# CAN.net
KiCad netlist of a schematic drawn in Altium Designer
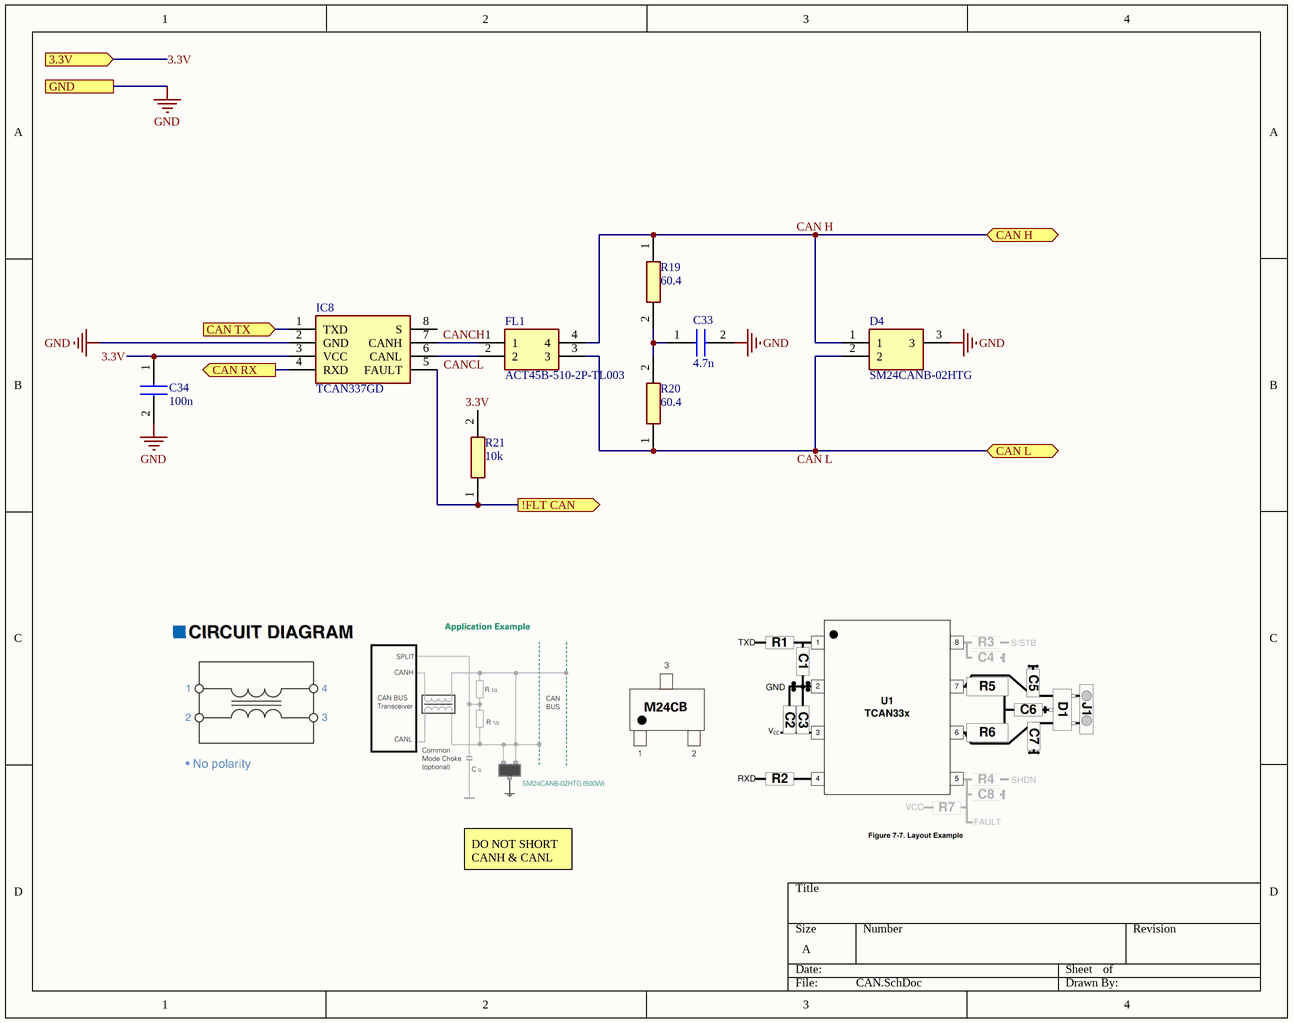
[diagram p0: CAN.SchDoc]

(export (version "E")
  (design (tool "Eeschema 10.0.6"))
  (components
    (comp (ref "C33")
      (value "4.7n")
      (footprint "SamacSys:CAPC3216X75N")
      (description "Capacitor")
      (fields
        (field (name "MANUFACTURER_PART_NUMBER") "KAM31GR71H475KL")
        (field (name "MOUSER PART NUMBER") "581-KAM31GR71H475KL")
      )
      (libsource (lib "*") (part "KAM31GR71H475KL"))
    )
    (comp (ref "C34")
      (value "100n")
      (footprint "SamacSys:CAPC3216X94N")
      (description "Capacitor")
      (fields
        (field (name "MANUFACTURER_PART_NUMBER") "12065C104J4Z2A")
        (field (name "MOUSER PART NUMBER") "581-12065C104J4Z2A")
      )
      (libsource (lib "SamacSys") (part "12065C104J4Z2A"))
    )
    (comp (ref "D4")
      (value "SM24CANB-02HTG")
      (footprint "SamacSys:SM24CANB02HTG")
      (description "TVS Diode (Bi-directional)")
      (fields (field (name "MOUSER PART NUMBER") "576-SM24CANB-02HTG"))
      (libsource (lib "*") (part "SM24CANB-02HTG"))
    )
    (comp (ref "FL1")
      (value "ACT45B-510-2P-TL003")
      (footprint "SamacSys:ACT45B1012PTL003")
      (description "Filter")
      (fields (field (name "MOUSER PART NUMBER") "810-ACT45B5102PTL003"))
      (libsource (lib "*") (part "ACT45B-510-2P-TL003"))
    )
    (comp (ref "IC8")
      (value "TCAN337GD")
      (footprint "SamacSys:SOIC127P600X175-8N")
      (description "Integrated Circuit")
      (fields (field (name "MOUSER PART NUMBER") "595-TCAN337GD"))
      (libsource (lib "*") (part "TCAN337GD"))
    )
    (comp (ref "R19")
      (value "60.4")
      (footprint "SamacSys:RESC3216X65N")
      (description "Resistor")
      (fields (field (name "MANUFACTURER_PART_NUMBER") "ESR18EZPF60R4"))
      (libsource (lib "*") (part "ESR18EZPF60R4"))
    )
    (comp (ref "R20")
      (value "60.4")
      (footprint "SamacSys:RESC3216X65N")
      (description "Resistor")
      (fields (field (name "MANUFACTURER_PART_NUMBER") "ESR18EZPF60R4"))
      (libsource (lib "") (part "ESR18EZPF60R4_1"))
    )
    (comp (ref "R21")
      (value "10k")
      (footprint "SamacSys:RESC3216X65N")
      (description "Resistor")
      (fields (field (name "MANUFACTURER_PART_NUMBER") "SFR18EZPJ103"))
      (libsource (lib "*") (part "SFR18EZPJ103"))
    )
  )
  (nets
    (net (code "1") (name "/!FLT CAN") (class "Default")
      (node (ref "IC8") (pin "5") (pinfunction "FAULT_5") (pintype "passive"))
      (node (ref "R21") (pin "1") (pinfunction "1_1") (pintype "passive"))
    )
    (net (code "2") (name "/3.3V") (class "Default")
      (node (ref "C34") (pin "1") (pinfunction "1_1") (pintype "passive"))
      (node (ref "IC8") (pin "3") (pinfunction "VCC_3") (pintype "passive"))
      (node (ref "R21") (pin "2") (pinfunction "2_2") (pintype "passive"))
    )
    (net (code "3") (name "/CAN H") (class "Default")
      (node (ref "D4") (pin "1") (pinfunction "1_1") (pintype "passive"))
      (node (ref "FL1") (pin "4") (pinfunction "4_4") (pintype "passive"))
      (node (ref "R19") (pin "1") (pinfunction "1_1") (pintype "passive"))
    )
    (net (code "4") (name "/CAN L") (class "Default")
      (node (ref "D4") (pin "2") (pinfunction "2_2") (pintype "passive"))
      (node (ref "FL1") (pin "3") (pinfunction "3_3") (pintype "passive"))
      (node (ref "R20") (pin "1") (pinfunction "1_1") (pintype "passive"))
    )
    (net (code "5") (name "/CAN RX") (class "Default")
      (node (ref "IC8") (pin "4") (pinfunction "RXD_4") (pintype "passive"))
    )
    (net (code "6") (name "/CAN TX") (class "Default")
      (node (ref "IC8") (pin "1") (pinfunction "TXD_1") (pintype "passive"))
    )
    (net (code "7") (name "/CANCH") (class "Default")
      (node (ref "FL1") (pin "1") (pinfunction "1_1") (pintype "passive"))
      (node (ref "IC8") (pin "7") (pinfunction "CANH_7") (pintype "passive"))
    )
    (net (code "8") (name "/CANCL") (class "Default")
      (node (ref "FL1") (pin "2") (pinfunction "2_2") (pintype "passive"))
      (node (ref "IC8") (pin "6") (pinfunction "CANL_6") (pintype "passive"))
    )
    (net (code "9") (name "GND") (class "Default")
      (node (ref "C33") (pin "2") (pinfunction "2_2") (pintype "passive"))
      (node (ref "C34") (pin "2") (pinfunction "2_2") (pintype "passive"))
      (node (ref "D4") (pin "3") (pinfunction "3_3") (pintype "passive"))
      (node (ref "IC8") (pin "2") (pinfunction "GND_2") (pintype "passive"))
    )
    (net (code "10") (name "Net-(C33-Pad1)") (class "Default")
      (node (ref "C33") (pin "1") (pinfunction "1_1") (pintype "passive"))
      (node (ref "R19") (pin "2") (pinfunction "2_2") (pintype "passive"))
      (node (ref "R20") (pin "2") (pinfunction "2_2") (pintype "passive"))
    )
    (net (code "11") (name "unconnected-(IC8-S-Pad8)") (class "Default")
      (node (ref "IC8") (pin "8") (pinfunction "S_8") (pintype "passive"))
    )
  )
)
